# Main.net
KiCad netlist of a schematic drawn in Altium Designer
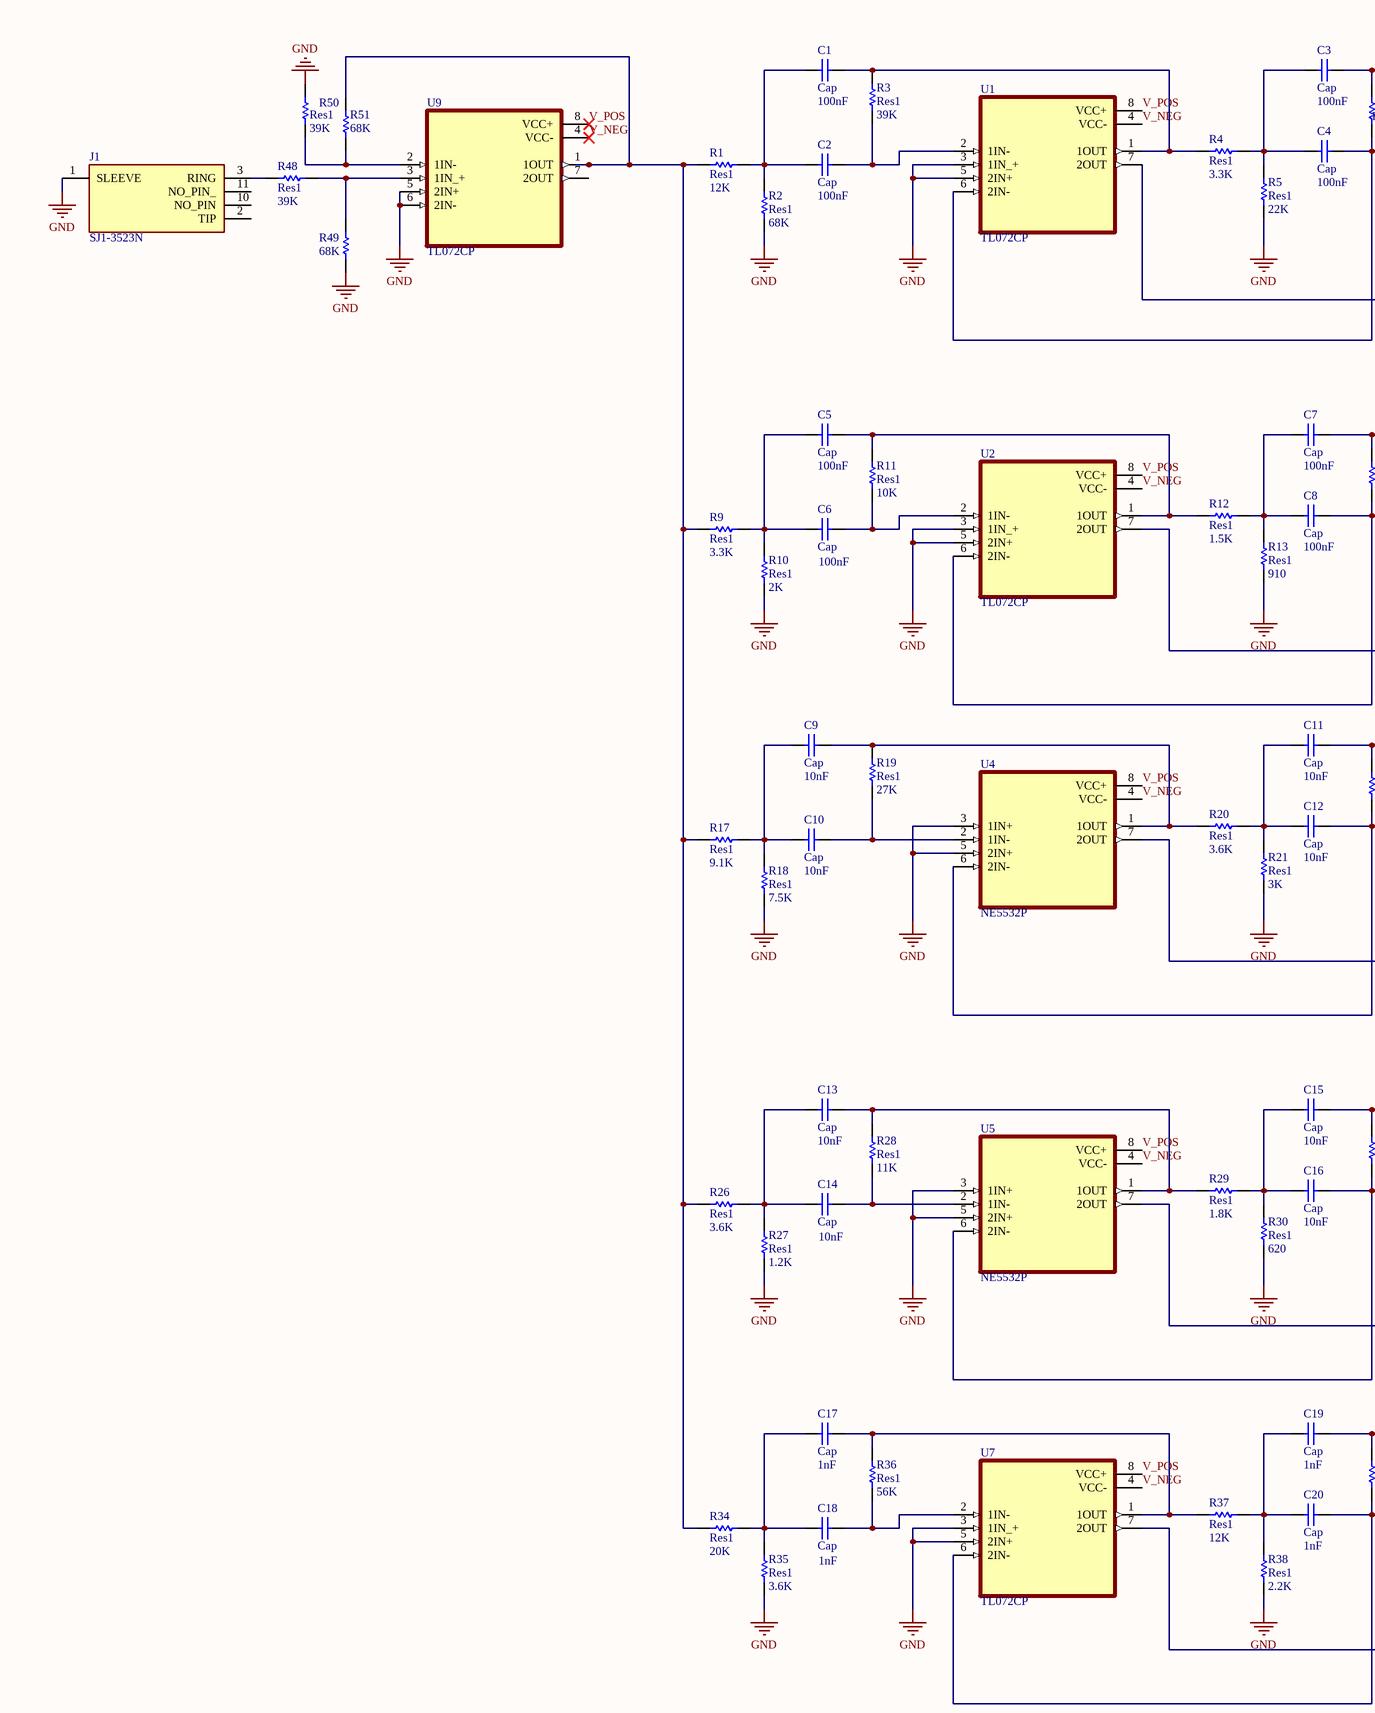
[diagram p0: Main.SchDoc, left]
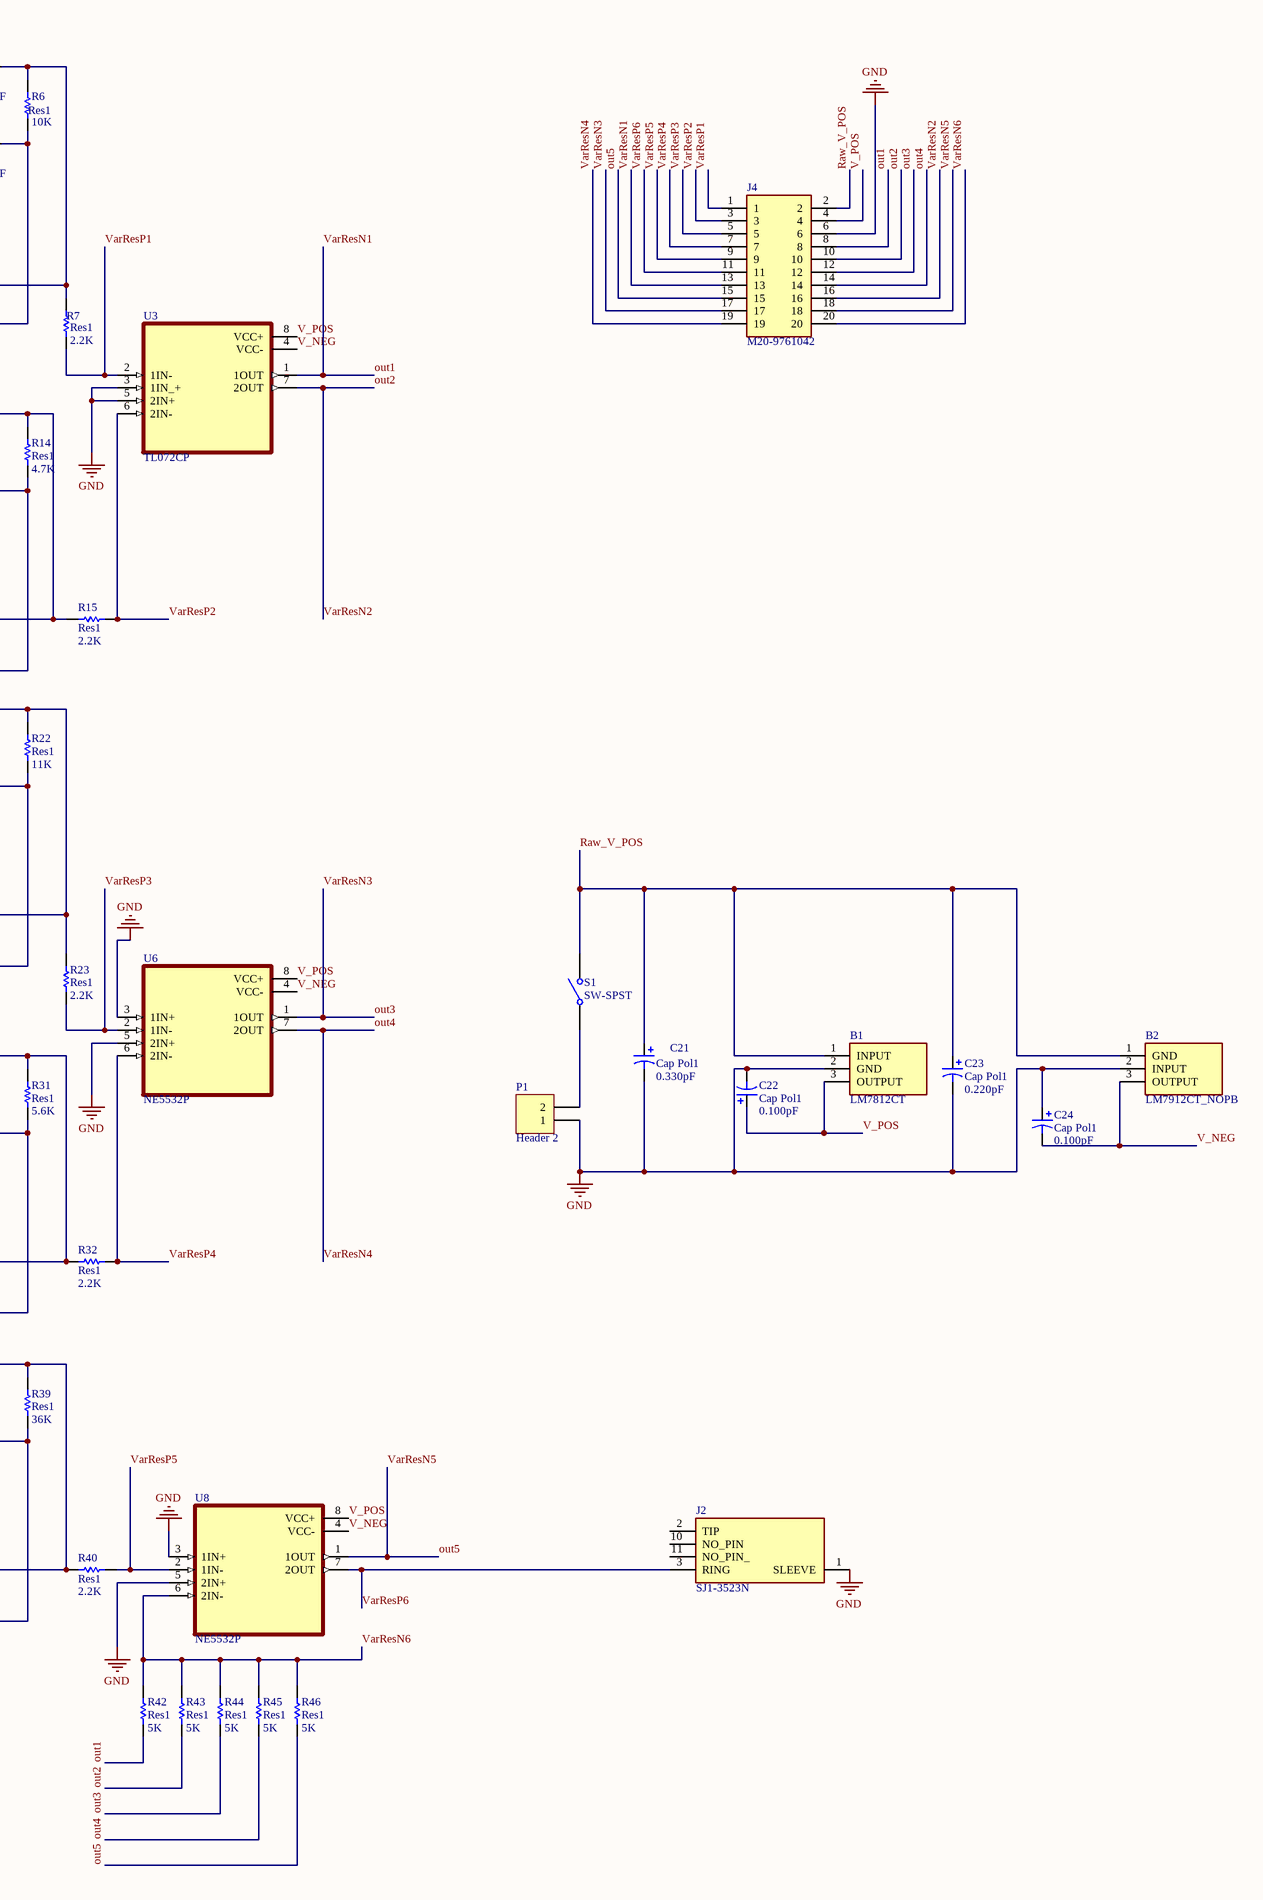
[diagram p1: Main.SchDoc, right]

(export (version "E")
  (design (tool "Eeschema 10.0.6"))
  (components
    (comp (ref "B1")
      (value "LM7812CT")
      (footprint "TO254P470X1028X1955-3P")
      (description "TO220 voltage regulator,LM7812CT 12V 1A")
      (fields (field (name "MOUSER PART NUMBER") "926-LM7812CT"))
      (libsource (lib "LM7812CT") (part "LM7812CT"))
    )
    (comp (ref "B2")
      (value "LM7912CT_NOPB")
      (footprint "TO254P470X1028X1955-3P")
      (description "Texas Instruments LM7912CT/NOPB, Single Negative Voltage Regulator 1.5A -12 V, +/-4%, 3-Pin TO-220")
      (fields
        (field (name "MANUFACTURER_PART_NUMBER") "LM7912CT/NOPB")
        (field (name "MOUSER PART NUMBER") "926-LM7912CT/NOPB")
      )
      (libsource (lib "LM7912CT_NOPB") (part "LM7912CT_NOPB"))
    )
    (comp (ref "C1")
      (value "Cap")
      (footprint "RAD-0.3")
      (description "Capacitor")
      (fields (field (name "ALTIUM_VALUE") "100nF") (field (name "PUBLISHER") "Altium Limited"))
      (libsource (lib "Miscellaneous Devices") (part "Cap"))
    )
    (comp (ref "C2")
      (value "Cap")
      (footprint "RAD-0.3")
      (description "Capacitor")
      (fields (field (name "ALTIUM_VALUE") "100nF") (field (name "PUBLISHER") "Altium Limited"))
      (libsource (lib "Miscellaneous Devices") (part "Cap"))
    )
    (comp (ref "C3")
      (value "Cap")
      (footprint "RAD-0.3")
      (description "Capacitor")
      (fields (field (name "ALTIUM_VALUE") "100nF") (field (name "PUBLISHER") "Altium Limited"))
      (libsource (lib "Miscellaneous Devices") (part "Cap"))
    )
    (comp (ref "C4")
      (value "Cap")
      (footprint "RAD-0.3")
      (description "Capacitor")
      (fields (field (name "ALTIUM_VALUE") "100nF") (field (name "PUBLISHER") "Altium Limited"))
      (libsource (lib "Miscellaneous Devices") (part "Cap"))
    )
    (comp (ref "C5")
      (value "Cap")
      (footprint "RAD-0.3")
      (description "Capacitor")
      (fields (field (name "ALTIUM_VALUE") "100nF") (field (name "PUBLISHER") "Altium Limited"))
      (libsource (lib "Miscellaneous Devices") (part "Cap"))
    )
    (comp (ref "C6")
      (value "Cap")
      (footprint "RAD-0.3")
      (description "Capacitor")
      (fields (field (name "ALTIUM_VALUE") "100nF") (field (name "PUBLISHER") "Altium Limited"))
      (libsource (lib "Miscellaneous Devices") (part "Cap"))
    )
    (comp (ref "C7")
      (value "Cap")
      (footprint "RAD-0.3")
      (description "Capacitor")
      (fields (field (name "ALTIUM_VALUE") "100nF") (field (name "PUBLISHER") "Altium Limited"))
      (libsource (lib "Miscellaneous Devices") (part "Cap"))
    )
    (comp (ref "C8")
      (value "Cap")
      (footprint "RAD-0.3")
      (description "Capacitor")
      (fields (field (name "ALTIUM_VALUE") "100nF") (field (name "PUBLISHER") "Altium Limited"))
      (libsource (lib "Miscellaneous Devices") (part "Cap"))
    )
    (comp (ref "C9")
      (value "Cap")
      (footprint "RAD-0.3")
      (description "Capacitor")
      (fields (field (name "ALTIUM_VALUE") "10nF") (field (name "PUBLISHER") "Altium Limited"))
      (libsource (lib "Miscellaneous Devices") (part "Cap"))
    )
    (comp (ref "C10")
      (value "Cap")
      (footprint "RAD-0.3")
      (description "Capacitor")
      (fields (field (name "ALTIUM_VALUE") "10nF") (field (name "PUBLISHER") "Altium Limited"))
      (libsource (lib "Miscellaneous Devices") (part "Cap"))
    )
    (comp (ref "C11")
      (value "Cap")
      (footprint "RAD-0.3")
      (description "Capacitor")
      (fields (field (name "ALTIUM_VALUE") "10nF") (field (name "PUBLISHER") "Altium Limited"))
      (libsource (lib "Miscellaneous Devices") (part "Cap"))
    )
    (comp (ref "C12")
      (value "Cap")
      (footprint "RAD-0.3")
      (description "Capacitor")
      (fields (field (name "ALTIUM_VALUE") "10nF") (field (name "PUBLISHER") "Altium Limited"))
      (libsource (lib "Miscellaneous Devices") (part "Cap"))
    )
    (comp (ref "C13")
      (value "Cap")
      (footprint "RAD-0.3")
      (description "Capacitor")
      (fields (field (name "ALTIUM_VALUE") "10nF") (field (name "PUBLISHER") "Altium Limited"))
      (libsource (lib "Miscellaneous Devices") (part "Cap"))
    )
    (comp (ref "C14")
      (value "Cap")
      (footprint "RAD-0.3")
      (description "Capacitor")
      (fields (field (name "ALTIUM_VALUE") "10nF") (field (name "PUBLISHER") "Altium Limited"))
      (libsource (lib "Miscellaneous Devices") (part "Cap"))
    )
    (comp (ref "C15")
      (value "Cap")
      (footprint "RAD-0.3")
      (description "Capacitor")
      (fields (field (name "ALTIUM_VALUE") "10nF") (field (name "PUBLISHER") "Altium Limited"))
      (libsource (lib "Miscellaneous Devices") (part "Cap"))
    )
    (comp (ref "C16")
      (value "Cap")
      (footprint "RAD-0.3")
      (description "Capacitor")
      (fields (field (name "ALTIUM_VALUE") "10nF") (field (name "PUBLISHER") "Altium Limited"))
      (libsource (lib "Miscellaneous Devices") (part "Cap"))
    )
    (comp (ref "C17")
      (value "Cap")
      (footprint "RAD-0.3")
      (description "Capacitor")
      (fields (field (name "ALTIUM_VALUE") "1nF") (field (name "PUBLISHER") "Altium Limited"))
      (libsource (lib "Miscellaneous Devices") (part "Cap"))
    )
    (comp (ref "C18")
      (value "Cap")
      (footprint "RAD-0.3")
      (description "Capacitor")
      (fields (field (name "ALTIUM_VALUE") "1nF") (field (name "PUBLISHER") "Altium Limited"))
      (libsource (lib "Miscellaneous Devices") (part "Cap"))
    )
    (comp (ref "C19")
      (value "Cap")
      (footprint "RAD-0.3")
      (description "Capacitor")
      (fields (field (name "ALTIUM_VALUE") "1nF") (field (name "PUBLISHER") "Altium Limited"))
      (libsource (lib "Miscellaneous Devices") (part "Cap"))
    )
    (comp (ref "C20")
      (value "Cap")
      (footprint "RAD-0.3")
      (description "Capacitor")
      (fields (field (name "ALTIUM_VALUE") "1nF") (field (name "PUBLISHER") "Altium Limited"))
      (libsource (lib "Miscellaneous Devices") (part "Cap"))
    )
    (comp (ref "C21")
      (value "Cap Pol1")
      (footprint "RB7.6-15")
      (description "Polarized Capacitor (Radial)")
      (fields (field (name "ALTIUM_VALUE") "0.330pF") (field (name "PUBLISHER") "Altium Limited"))
      (libsource (lib "Miscellaneous Devices") (part "Cap Pol1"))
    )
    (comp (ref "C22")
      (value "Cap Pol1")
      (footprint "RB7.6-15")
      (description "Polarized Capacitor (Radial)")
      (fields (field (name "ALTIUM_VALUE") "0.100pF") (field (name "PUBLISHER") "Altium Limited"))
      (libsource (lib "Miscellaneous Devices") (part "Cap Pol1"))
    )
    (comp (ref "C23")
      (value "Cap Pol1")
      (footprint "RB7.6-15")
      (description "Polarized Capacitor (Radial)")
      (fields (field (name "ALTIUM_VALUE") "0.220pF") (field (name "PUBLISHER") "Altium Limited"))
      (libsource (lib "Miscellaneous Devices") (part "Cap Pol1"))
    )
    (comp (ref "C24")
      (value "Cap Pol1")
      (footprint "RB7.6-15")
      (description "Polarized Capacitor (Radial)")
      (fields (field (name "ALTIUM_VALUE") "0.100pF") (field (name "PUBLISHER") "Altium Limited"))
      (libsource (lib "Miscellaneous Devices") (part "Cap Pol1"))
    )
    (comp (ref "J1")
      (value "SJ1-3523N")
      (footprint "SJ13523N")
      (description "Phone Connectors 3.5 MM AUDIO JACK")
      (fields (field (name "MOUSER PART NUMBER") "490-SJ1-3523N"))
      (libsource (lib "") (part "SJ1-3523N_1"))
    )
    (comp (ref "J2")
      (value "SJ1-3523N")
      (footprint "SJ13523N")
      (description "Phone Connectors 3.5 MM AUDIO JACK")
      (fields (field (name "MOUSER PART NUMBER") "490-SJ1-3523N"))
      (libsource (lib "SJ1-3523N") (part "SJ1-3523N"))
    )
    (comp (ref "J4")
      (value "M20-9761042")
      (footprint "HDRV20W64P254_2X10_2540X508X838P")
      (description "Headers & Wire Housings 10+10 DIL VERTICAL PIN HEADER GOLD+TIN")
      (fields (field (name "MOUSER PART NUMBER") "855-M20-9761042"))
      (libsource (lib "M20-9761042") (part "M20-9761042"))
    )
    (comp (ref "P1")
      (value "Header 2")
      (footprint "HDR1X2")
      (description "Header, 2-Pin")
      (fields (field (name "PUBLISHER") "Altium Limited"))
      (libsource (lib "Miscellaneous Connectors") (part "Header 2"))
    )
    (comp (ref "R1")
      (value "Res1")
      (footprint "AXIAL-0.3")
      (description "Resistor")
      (fields (field (name "ALTIUM_VALUE") "12K") (field (name "PUBLISHER") "Altium Limited"))
      (libsource (lib "Miscellaneous Devices") (part "Res1"))
    )
    (comp (ref "R2")
      (value "Res1")
      (footprint "AXIAL-0.3")
      (description "Resistor")
      (fields (field (name "ALTIUM_VALUE") "68K") (field (name "PUBLISHER") "Altium Limited"))
      (libsource (lib "Miscellaneous Devices") (part "Res1"))
    )
    (comp (ref "R3")
      (value "Res1")
      (footprint "AXIAL-0.3")
      (description "Resistor")
      (fields (field (name "ALTIUM_VALUE") "39K") (field (name "PUBLISHER") "Altium Limited"))
      (libsource (lib "Miscellaneous Devices") (part "Res1"))
    )
    (comp (ref "R4")
      (value "Res1")
      (footprint "AXIAL-0.3")
      (description "Resistor")
      (fields (field (name "ALTIUM_VALUE") "3.3K") (field (name "PUBLISHER") "Altium Limited"))
      (libsource (lib "Miscellaneous Devices") (part "Res1"))
    )
    (comp (ref "R5")
      (value "Res1")
      (footprint "AXIAL-0.3")
      (description "Resistor")
      (fields (field (name "ALTIUM_VALUE") "22K") (field (name "PUBLISHER") "Altium Limited"))
      (libsource (lib "Miscellaneous Devices") (part "Res1"))
    )
    (comp (ref "R6")
      (value "Res1")
      (footprint "AXIAL-0.3")
      (description "Resistor")
      (fields (field (name "ALTIUM_VALUE") "10K") (field (name "PUBLISHER") "Altium Limited"))
      (libsource (lib "Miscellaneous Devices") (part "Res1"))
    )
    (comp (ref "R7")
      (value "Res1")
      (footprint "AXIAL-0.3")
      (description "Resistor")
      (fields (field (name "ALTIUM_VALUE") "2.2K") (field (name "PUBLISHER") "Altium Limited"))
      (libsource (lib "Miscellaneous Devices") (part "Res1"))
    )
    (comp (ref "R9")
      (value "Res1")
      (footprint "AXIAL-0.3")
      (description "Resistor")
      (fields (field (name "ALTIUM_VALUE") "3.3K") (field (name "PUBLISHER") "Altium Limited"))
      (libsource (lib "") (part "Res1_1"))
    )
    (comp (ref "R10")
      (value "Res1")
      (footprint "AXIAL-0.3")
      (description "Resistor")
      (fields (field (name "ALTIUM_VALUE") "2K") (field (name "PUBLISHER") "Altium Limited"))
      (libsource (lib "Miscellaneous Devices") (part "Res1"))
    )
    (comp (ref "R11")
      (value "Res1")
      (footprint "AXIAL-0.3")
      (description "Resistor")
      (fields (field (name "ALTIUM_VALUE") "10K") (field (name "PUBLISHER") "Altium Limited"))
      (libsource (lib "Miscellaneous Devices") (part "Res1"))
    )
    (comp (ref "R12")
      (value "Res1")
      (footprint "AXIAL-0.3")
      (description "Resistor")
      (fields (field (name "ALTIUM_VALUE") "1.5K") (field (name "PUBLISHER") "Altium Limited"))
      (libsource (lib "") (part "Res1_1"))
    )
    (comp (ref "R13")
      (value "Res1")
      (footprint "AXIAL-0.3")
      (description "Resistor")
      (fields (field (name "ALTIUM_VALUE") "910") (field (name "PUBLISHER") "Altium Limited"))
      (libsource (lib "Miscellaneous Devices") (part "Res1"))
    )
    (comp (ref "R14")
      (value "Res1")
      (footprint "AXIAL-0.3")
      (description "Resistor")
      (fields (field (name "ALTIUM_VALUE") "4.7K") (field (name "PUBLISHER") "Altium Limited"))
      (libsource (lib "Miscellaneous Devices") (part "Res1"))
    )
    (comp (ref "R15")
      (value "Res1")
      (footprint "AXIAL-0.3")
      (description "Resistor")
      (fields (field (name "ALTIUM_VALUE") "2.2K") (field (name "PUBLISHER") "Altium Limited"))
      (libsource (lib "") (part "Res1_1"))
    )
    (comp (ref "R17")
      (value "Res1")
      (footprint "AXIAL-0.3")
      (description "Resistor")
      (fields (field (name "ALTIUM_VALUE") "9.1K") (field (name "PUBLISHER") "Altium Limited"))
      (libsource (lib "Miscellaneous Devices") (part "Res1"))
    )
    (comp (ref "R18")
      (value "Res1")
      (footprint "AXIAL-0.3")
      (description "Resistor")
      (fields (field (name "ALTIUM_VALUE") "7.5K") (field (name "PUBLISHER") "Altium Limited"))
      (libsource (lib "Miscellaneous Devices") (part "Res1"))
    )
    (comp (ref "R19")
      (value "Res1")
      (footprint "AXIAL-0.3")
      (description "Resistor")
      (fields (field (name "ALTIUM_VALUE") "27K") (field (name "PUBLISHER") "Altium Limited"))
      (libsource (lib "Miscellaneous Devices") (part "Res1"))
    )
    (comp (ref "R20")
      (value "Res1")
      (footprint "AXIAL-0.3")
      (description "Resistor")
      (fields (field (name "ALTIUM_VALUE") "3.6K") (field (name "PUBLISHER") "Altium Limited"))
      (libsource (lib "Miscellaneous Devices") (part "Res1"))
    )
    (comp (ref "R21")
      (value "Res1")
      (footprint "AXIAL-0.3")
      (description "Resistor")
      (fields (field (name "ALTIUM_VALUE") "3K") (field (name "PUBLISHER") "Altium Limited"))
      (libsource (lib "Miscellaneous Devices") (part "Res1"))
    )
    (comp (ref "R22")
      (value "Res1")
      (footprint "AXIAL-0.3")
      (description "Resistor")
      (fields (field (name "ALTIUM_VALUE") "11K") (field (name "PUBLISHER") "Altium Limited"))
      (libsource (lib "Miscellaneous Devices") (part "Res1"))
    )
    (comp (ref "R23")
      (value "Res1")
      (footprint "AXIAL-0.3")
      (description "Resistor")
      (fields (field (name "ALTIUM_VALUE") "2.2K") (field (name "PUBLISHER") "Altium Limited"))
      (libsource (lib "Miscellaneous Devices") (part "Res1"))
    )
    (comp (ref "R26")
      (value "Res1")
      (footprint "AXIAL-0.3")
      (description "Resistor")
      (fields (field (name "ALTIUM_VALUE") "3.6K") (field (name "PUBLISHER") "Altium Limited"))
      (libsource (lib "Miscellaneous Devices") (part "Res1"))
    )
    (comp (ref "R27")
      (value "Res1")
      (footprint "AXIAL-0.3")
      (description "Resistor")
      (fields (field (name "ALTIUM_VALUE") "1.2K") (field (name "PUBLISHER") "Altium Limited"))
      (libsource (lib "Miscellaneous Devices") (part "Res1"))
    )
    (comp (ref "R28")
      (value "Res1")
      (footprint "AXIAL-0.3")
      (description "Resistor")
      (fields (field (name "ALTIUM_VALUE") "11K") (field (name "PUBLISHER") "Altium Limited"))
      (libsource (lib "Miscellaneous Devices") (part "Res1"))
    )
    (comp (ref "R29")
      (value "Res1")
      (footprint "AXIAL-0.3")
      (description "Resistor")
      (fields (field (name "ALTIUM_VALUE") "1.8K") (field (name "PUBLISHER") "Altium Limited"))
      (libsource (lib "Miscellaneous Devices") (part "Res1"))
    )
    (comp (ref "R30")
      (value "Res1")
      (footprint "AXIAL-0.3")
      (description "Resistor")
      (fields (field (name "ALTIUM_VALUE") "620") (field (name "PUBLISHER") "Altium Limited"))
      (libsource (lib "Miscellaneous Devices") (part "Res1"))
    )
    (comp (ref "R31")
      (value "Res1")
      (footprint "AXIAL-0.3")
      (description "Resistor")
      (fields (field (name "ALTIUM_VALUE") "5.6K") (field (name "PUBLISHER") "Altium Limited"))
      (libsource (lib "Miscellaneous Devices") (part "Res1"))
    )
    (comp (ref "R32")
      (value "Res1")
      (footprint "AXIAL-0.3")
      (description "Resistor")
      (fields (field (name "ALTIUM_VALUE") "2.2K") (field (name "PUBLISHER") "Altium Limited"))
      (libsource (lib "Miscellaneous Devices") (part "Res1"))
    )
    (comp (ref "R34")
      (value "Res1")
      (footprint "AXIAL-0.3")
      (description "Resistor")
      (fields (field (name "ALTIUM_VALUE") "20K") (field (name "PUBLISHER") "Altium Limited"))
      (libsource (lib "Miscellaneous Devices") (part "Res1"))
    )
    (comp (ref "R35")
      (value "Res1")
      (footprint "AXIAL-0.3")
      (description "Resistor")
      (fields (field (name "ALTIUM_VALUE") "3.6K") (field (name "PUBLISHER") "Altium Limited"))
      (libsource (lib "Miscellaneous Devices") (part "Res1"))
    )
    (comp (ref "R36")
      (value "Res1")
      (footprint "AXIAL-0.3")
      (description "Resistor")
      (fields (field (name "ALTIUM_VALUE") "56K") (field (name "PUBLISHER") "Altium Limited"))
      (libsource (lib "Miscellaneous Devices") (part "Res1"))
    )
    (comp (ref "R37")
      (value "Res1")
      (footprint "AXIAL-0.3")
      (description "Resistor")
      (fields (field (name "ALTIUM_VALUE") "12K") (field (name "PUBLISHER") "Altium Limited"))
      (libsource (lib "Miscellaneous Devices") (part "Res1"))
    )
    (comp (ref "R38")
      (value "Res1")
      (footprint "AXIAL-0.3")
      (description "Resistor")
      (fields (field (name "ALTIUM_VALUE") "2.2K") (field (name "PUBLISHER") "Altium Limited"))
      (libsource (lib "Miscellaneous Devices") (part "Res1"))
    )
    (comp (ref "R39")
      (value "Res1")
      (footprint "AXIAL-0.3")
      (description "Resistor")
      (fields (field (name "ALTIUM_VALUE") "36K") (field (name "PUBLISHER") "Altium Limited"))
      (libsource (lib "") (part "Res1_1"))
    )
    (comp (ref "R40")
      (value "Res1")
      (footprint "AXIAL-0.3")
      (description "Resistor")
      (fields (field (name "ALTIUM_VALUE") "2.2K") (field (name "PUBLISHER") "Altium Limited"))
      (libsource (lib "Miscellaneous Devices") (part "Res1"))
    )
    (comp (ref "R42")
      (value "Res1")
      (footprint "AXIAL-0.3")
      (description "Resistor")
      (fields (field (name "ALTIUM_VALUE") "5K") (field (name "PUBLISHER") "Altium Limited"))
      (libsource (lib "Miscellaneous Devices") (part "Res1"))
    )
    (comp (ref "R43")
      (value "Res1")
      (footprint "AXIAL-0.3")
      (description "Resistor")
      (fields (field (name "ALTIUM_VALUE") "5K") (field (name "PUBLISHER") "Altium Limited"))
      (libsource (lib "Miscellaneous Devices") (part "Res1"))
    )
    (comp (ref "R44")
      (value "Res1")
      (footprint "AXIAL-0.3")
      (description "Resistor")
      (fields (field (name "ALTIUM_VALUE") "5K") (field (name "PUBLISHER") "Altium Limited"))
      (libsource (lib "Miscellaneous Devices") (part "Res1"))
    )
    (comp (ref "R45")
      (value "Res1")
      (footprint "AXIAL-0.3")
      (description "Resistor")
      (fields (field (name "ALTIUM_VALUE") "5K") (field (name "PUBLISHER") "Altium Limited"))
      (libsource (lib "Miscellaneous Devices") (part "Res1"))
    )
    (comp (ref "R46")
      (value "Res1")
      (footprint "AXIAL-0.3")
      (description "Resistor")
      (fields (field (name "ALTIUM_VALUE") "5K") (field (name "PUBLISHER") "Altium Limited"))
      (libsource (lib "Miscellaneous Devices") (part "Res1"))
    )
    (comp (ref "R48")
      (value "Res1")
      (footprint "AXIAL-0.3")
      (description "Resistor")
      (fields (field (name "ALTIUM_VALUE") "39K") (field (name "PUBLISHER") "Altium Limited"))
      (libsource (lib "Miscellaneous Devices") (part "Res1"))
    )
    (comp (ref "R49")
      (value "68K")
      (footprint "AXIAL-0.3")
      (description "Resistor")
      (fields (field (name "Comment") "Res1") (field (name "PUBLISHER") "Altium Limited"))
      (libsource (lib "Miscellaneous Devices") (part "Res1"))
    )
    (comp (ref "R50")
      (value "Res1")
      (footprint "AXIAL-0.3")
      (description "Resistor")
      (fields (field (name "ALTIUM_VALUE") "39K") (field (name "PUBLISHER") "Altium Limited"))
      (libsource (lib "Miscellaneous Devices") (part "Res1"))
    )
    (comp (ref "R51")
      (value "68K")
      (footprint "AXIAL-0.3")
      (description "Resistor")
      (fields (field (name "Comment") "Res1") (field (name "PUBLISHER") "Altium Limited"))
      (libsource (lib "Miscellaneous Devices") (part "Res1"))
    )
    (comp (ref "S1")
      (value "SW-SPST")
      (footprint "SPST-2")
      (description "Single-Pole, Single-Throw Switch")
      (fields (field (name "PUBLISHER") "Altium Limited"))
      (libsource (lib "Miscellaneous Devices") (part "SW-SPST"))
    )
    (comp (ref "U1")
      (value "TL072CP")
      (footprint "DIP794W45P254L959H508Q8")
      (description "Dual Low-Noise JFET-Input General-Purpose Operational Amplifier")
      (fields (field (name "MF") "Texas Instruments"))
      (libsource (lib "TL072CP") (part "TL072CP"))
    )
    (comp (ref "U2")
      (value "TL072CP")
      (footprint "DIP794W45P254L959H508Q8")
      (description "Dual Low-Noise JFET-Input General-Purpose Operational Amplifier")
      (fields (field (name "MF") "Texas Instruments"))
      (libsource (lib "TL072CP") (part "TL072CP"))
    )
    (comp (ref "U3")
      (value "TL072CP")
      (footprint "DIP794W45P254L959H508Q8")
      (description "Dual Low-Noise JFET-Input General-Purpose Operational Amplifier")
      (fields (field (name "MF") "Texas Instruments"))
      (libsource (lib "TL072CP") (part "TL072CP"))
    )
    (comp (ref "U4")
      (value "NE5532P")
      (footprint "DIP794W45P254L959H508Q8")
      (description "Dual Low-Noise High-Speed Audio Operational Amplifier 8-PDIP 0 to 70")
      (fields (field (name "MF") "Texas Instruments"))
      (libsource (lib "NE5532P") (part "NE5532P"))
    )
    (comp (ref "U5")
      (value "NE5532P")
      (footprint "DIP794W45P254L959H508Q8")
      (description "Dual Low-Noise High-Speed Audio Operational Amplifier 8-PDIP 0 to 70")
      (fields (field (name "MF") "Texas Instruments"))
      (libsource (lib "NE5532P") (part "NE5532P"))
    )
    (comp (ref "U6")
      (value "NE5532P")
      (footprint "DIP794W45P254L959H508Q8")
      (description "Dual Low-Noise High-Speed Audio Operational Amplifier 8-PDIP 0 to 70")
      (fields (field (name "MF") "Texas Instruments"))
      (libsource (lib "NE5532P") (part "NE5532P"))
    )
    (comp (ref "U7")
      (value "TL072CP")
      (footprint "DIP794W45P254L959H508Q8")
      (description "Dual Low-Noise JFET-Input General-Purpose Operational Amplifier")
      (fields (field (name "MF") "Texas Instruments"))
      (libsource (lib "TL072CP") (part "TL072CP"))
    )
    (comp (ref "U8")
      (value "NE5532P")
      (footprint "DIP794W45P254L959H508Q8")
      (description "Dual Low-Noise High-Speed Audio Operational Amplifier 8-PDIP 0 to 70")
      (fields (field (name "MF") "Texas Instruments"))
      (libsource (lib "NE5532P") (part "NE5532P"))
    )
    (comp (ref "U9")
      (value "TL072CP")
      (footprint "DIP794W45P254L959H508Q8")
      (description "Dual Low-Noise JFET-Input General-Purpose Operational Amplifier")
      (fields (field (name "MF") "Texas Instruments"))
      (libsource (lib "TL072CP") (part "TL072CP"))
    )
  )
  (nets
    (net (code "1") (name "/Raw_V_POS") (class "Default")
      (node (ref "B1") (pin "1") (pinfunction "INPUT_1") (pintype "passive"))
      (node (ref "B2") (pin "1") (pinfunction "GND_1") (pintype "passive"))
      (node (ref "C21") (pin "1") (pinfunction "1_1") (pintype "passive"))
      (node (ref "C23") (pin "1") (pinfunction "1_1") (pintype "passive"))
      (node (ref "J4") (pin "2") (pinfunction "2_2") (pintype "passive"))
      (node (ref "S1") (pin "2") (pinfunction "NO_2") (pintype "passive"))
    )
    (net (code "2") (name "/V_NEG") (class "Default")
      (node (ref "B2") (pin "3") (pinfunction "OUTPUT_3") (pintype "passive"))
      (node (ref "C24") (pin "2") (pinfunction "2_2") (pintype "passive"))
      (node (ref "U1") (pin "4") (pinfunction "VCC-_4") (pintype "power_in"))
      (node (ref "U2") (pin "4") (pinfunction "VCC-_4") (pintype "power_in"))
      (node (ref "U3") (pin "4") (pinfunction "VCC-_4") (pintype "power_in"))
      (node (ref "U4") (pin "4") (pinfunction "VCC-_4") (pintype "power_in"))
      (node (ref "U5") (pin "4") (pinfunction "VCC-_4") (pintype "power_in"))
      (node (ref "U6") (pin "4") (pinfunction "VCC-_4") (pintype "power_in"))
      (node (ref "U7") (pin "4") (pinfunction "VCC-_4") (pintype "power_in"))
      (node (ref "U8") (pin "4") (pinfunction "VCC-_4") (pintype "power_in"))
      (node (ref "U9") (pin "4") (pinfunction "VCC-_4") (pintype "power_in"))
    )
    (net (code "3") (name "/V_POS") (class "Default")
      (node (ref "B1") (pin "3") (pinfunction "OUTPUT_3") (pintype "passive"))
      (node (ref "C22") (pin "1") (pinfunction "1_1") (pintype "passive"))
      (node (ref "J4") (pin "4") (pinfunction "4_4") (pintype "passive"))
      (node (ref "U1") (pin "8") (pinfunction "VCC+_8") (pintype "power_in"))
      (node (ref "U2") (pin "8") (pinfunction "VCC+_8") (pintype "power_in"))
      (node (ref "U3") (pin "8") (pinfunction "VCC+_8") (pintype "power_in"))
      (node (ref "U4") (pin "8") (pinfunction "VCC+_8") (pintype "power_in"))
      (node (ref "U5") (pin "8") (pinfunction "VCC+_8") (pintype "power_in"))
      (node (ref "U6") (pin "8") (pinfunction "VCC+_8") (pintype "power_in"))
      (node (ref "U7") (pin "8") (pinfunction "VCC+_8") (pintype "power_in"))
      (node (ref "U8") (pin "8") (pinfunction "VCC+_8") (pintype "power_in"))
      (node (ref "U9") (pin "8") (pinfunction "VCC+_8") (pintype "power_in"))
    )
    (net (code "4") (name "/VarResN1") (class "Default")
      (node (ref "J4") (pin "13") (pinfunction "13_13") (pintype "passive"))
      (node (ref "J4") (pin "8") (pinfunction "8_8") (pintype "passive"))
      (node (ref "R42") (pin "1") (pinfunction "1_1") (pintype "passive"))
      (node (ref "U3") (pin "1") (pinfunction "1OUT_1") (pintype "output"))
    )
    (net (code "5") (name "/VarResN2") (class "Default")
      (node (ref "J4") (pin "10") (pinfunction "10_10") (pintype "passive"))
      (node (ref "J4") (pin "16") (pinfunction "16_16") (pintype "passive"))
      (node (ref "R43") (pin "1") (pinfunction "1_1") (pintype "passive"))
      (node (ref "U3") (pin "7") (pinfunction "2OUT_7") (pintype "output"))
    )
    (net (code "6") (name "/VarResN3") (class "Default")
      (node (ref "J4") (pin "12") (pinfunction "12_12") (pintype "passive"))
      (node (ref "J4") (pin "17") (pinfunction "17_17") (pintype "passive"))
      (node (ref "R44") (pin "1") (pinfunction "1_1") (pintype "passive"))
      (node (ref "U6") (pin "1") (pinfunction "1OUT_1") (pintype "output"))
    )
    (net (code "7") (name "/VarResN4") (class "Default")
      (node (ref "J4") (pin "14") (pinfunction "14_14") (pintype "passive"))
      (node (ref "J4") (pin "19") (pinfunction "19_19") (pintype "passive"))
      (node (ref "R45") (pin "1") (pinfunction "1_1") (pintype "passive"))
      (node (ref "U6") (pin "7") (pinfunction "2OUT_7") (pintype "output"))
    )
    (net (code "8") (name "/VarResN5") (class "Default")
      (node (ref "J4") (pin "15") (pinfunction "15_15") (pintype "passive"))
      (node (ref "J4") (pin "18") (pinfunction "18_18") (pintype "passive"))
      (node (ref "R46") (pin "1") (pinfunction "1_1") (pintype "passive"))
      (node (ref "U8") (pin "1") (pinfunction "1OUT_1") (pintype "output"))
    )
    (net (code "9") (name "/VarResN6") (class "Default")
      (node (ref "J4") (pin "20") (pinfunction "20_20") (pintype "passive"))
      (node (ref "R42") (pin "2") (pinfunction "2_2") (pintype "passive"))
      (node (ref "R43") (pin "2") (pinfunction "2_2") (pintype "passive"))
      (node (ref "R44") (pin "2") (pinfunction "2_2") (pintype "passive"))
      (node (ref "R45") (pin "2") (pinfunction "2_2") (pintype "passive"))
      (node (ref "R46") (pin "2") (pinfunction "2_2") (pintype "passive"))
      (node (ref "U8") (pin "6") (pinfunction "2IN-_6") (pintype "input"))
    )
    (net (code "10") (name "/VarResP1") (class "Default")
      (node (ref "J4") (pin "1") (pinfunction "1_1") (pintype "passive"))
      (node (ref "R7") (pin "1") (pinfunction "1_1") (pintype "passive"))
      (node (ref "U3") (pin "2") (pinfunction "1IN-_2") (pintype "input"))
    )
    (net (code "11") (name "/VarResP2") (class "Default")
      (node (ref "J4") (pin "3") (pinfunction "3_3") (pintype "passive"))
      (node (ref "R15") (pin "2") (pinfunction "2_2") (pintype "passive"))
      (node (ref "U3") (pin "6") (pinfunction "2IN-_6") (pintype "input"))
    )
    (net (code "12") (name "/VarResP3") (class "Default")
      (node (ref "J4") (pin "5") (pinfunction "5_5") (pintype "passive"))
      (node (ref "R23") (pin "1") (pinfunction "1_1") (pintype "passive"))
      (node (ref "U6") (pin "2") (pinfunction "1IN-_2") (pintype "input"))
    )
    (net (code "13") (name "/VarResP4") (class "Default")
      (node (ref "J4") (pin "7") (pinfunction "7_7") (pintype "passive"))
      (node (ref "R32") (pin "1") (pinfunction "1_1") (pintype "passive"))
      (node (ref "U6") (pin "6") (pinfunction "2IN-_6") (pintype "input"))
    )
    (net (code "14") (name "/VarResP5") (class "Default")
      (node (ref "J4") (pin "9") (pinfunction "9_9") (pintype "passive"))
      (node (ref "R40") (pin "1") (pinfunction "1_1") (pintype "passive"))
      (node (ref "U8") (pin "2") (pinfunction "1IN-_2") (pintype "input"))
    )
    (net (code "15") (name "/VarResP6") (class "Default")
      (node (ref "J2") (pin "3") (pinfunction "RING_3") (pintype "passive"))
      (node (ref "J4") (pin "11") (pinfunction "11_11") (pintype "passive"))
      (node (ref "U8") (pin "7") (pinfunction "2OUT_7") (pintype "output"))
    )
    (net (code "16") (name "GND") (class "Default")
      (node (ref "B1") (pin "2") (pinfunction "GND_2") (pintype "passive"))
      (node (ref "B2") (pin "2") (pinfunction "INPUT_2") (pintype "passive"))
      (node (ref "C21") (pin "2") (pinfunction "2_2") (pintype "passive"))
      (node (ref "C22") (pin "2") (pinfunction "2_2") (pintype "passive"))
      (node (ref "C23") (pin "2") (pinfunction "2_2") (pintype "passive"))
      (node (ref "C24") (pin "1") (pinfunction "1_1") (pintype "passive"))
      (node (ref "J1") (pin "1") (pinfunction "SLEEVE_1") (pintype "passive"))
      (node (ref "J2") (pin "1") (pinfunction "SLEEVE_1") (pintype "passive"))
      (node (ref "J4") (pin "6") (pinfunction "6_6") (pintype "passive"))
      (node (ref "P1") (pin "1") (pinfunction "1_1") (pintype "passive"))
      (node (ref "R10") (pin "1") (pinfunction "1_1") (pintype "passive"))
      (node (ref "R13") (pin "1") (pinfunction "1_1") (pintype "passive"))
      (node (ref "R18") (pin "1") (pinfunction "1_1") (pintype "passive"))
      (node (ref "R2") (pin "1") (pinfunction "1_1") (pintype "passive"))
      (node (ref "R21") (pin "1") (pinfunction "1_1") (pintype "passive"))
      (node (ref "R27") (pin "1") (pinfunction "1_1") (pintype "passive"))
      (node (ref "R30") (pin "1") (pinfunction "1_1") (pintype "passive"))
      (node (ref "R35") (pin "1") (pinfunction "1_1") (pintype "passive"))
      (node (ref "R38") (pin "1") (pinfunction "1_1") (pintype "passive"))
      (node (ref "R49") (pin "2") (pinfunction "2_2") (pintype "passive"))
      (node (ref "R5") (pin "1") (pinfunction "1_1") (pintype "passive"))
      (node (ref "R50") (pin "2") (pinfunction "2_2") (pintype "passive"))
      (node (ref "U1") (pin "3") (pinfunction "1IN_+_3") (pintype "input"))
      (node (ref "U1") (pin "5") (pinfunction "2IN+_5") (pintype "input"))
      (node (ref "U2") (pin "3") (pinfunction "1IN_+_3") (pintype "input"))
      (node (ref "U2") (pin "5") (pinfunction "2IN+_5") (pintype "input"))
      (node (ref "U3") (pin "3") (pinfunction "1IN_+_3") (pintype "input"))
      (node (ref "U3") (pin "5") (pinfunction "2IN+_5") (pintype "input"))
      (node (ref "U4") (pin "3") (pinfunction "1IN+_3") (pintype "input"))
      (node (ref "U4") (pin "5") (pinfunction "2IN+_5") (pintype "input"))
      (node (ref "U5") (pin "3") (pinfunction "1IN+_3") (pintype "input"))
      (node (ref "U5") (pin "5") (pinfunction "2IN+_5") (pintype "input"))
      (node (ref "U6") (pin "3") (pinfunction "1IN+_3") (pintype "input"))
      (node (ref "U6") (pin "5") (pinfunction "2IN+_5") (pintype "input"))
      (node (ref "U7") (pin "3") (pinfunction "1IN_+_3") (pintype "input"))
      (node (ref "U7") (pin "5") (pinfunction "2IN+_5") (pintype "input"))
      (node (ref "U8") (pin "3") (pinfunction "1IN+_3") (pintype "input"))
      (node (ref "U8") (pin "5") (pinfunction "2IN+_5") (pintype "input"))
      (node (ref "U9") (pin "5") (pinfunction "2IN+_5") (pintype "input"))
      (node (ref "U9") (pin "6") (pinfunction "2IN-_6") (pintype "input"))
    )
    (net (code "17") (name "Net-(C1-Pad1)") (class "Default")
      (node (ref "C1") (pin "1") (pinfunction "1_1") (pintype "passive"))
      (node (ref "C2") (pin "1") (pinfunction "1_1") (pintype "passive"))
      (node (ref "R1") (pin "2") (pinfunction "2_2") (pintype "passive"))
      (node (ref "R2") (pin "2") (pinfunction "2_2") (pintype "passive"))
    )
    (net (code "18") (name "Net-(C3-Pad1)") (class "Default")
      (node (ref "C3") (pin "1") (pinfunction "1_1") (pintype "passive"))
      (node (ref "C4") (pin "1") (pinfunction "1_1") (pintype "passive"))
      (node (ref "R4") (pin "2") (pinfunction "2_2") (pintype "passive"))
      (node (ref "R5") (pin "2") (pinfunction "2_2") (pintype "passive"))
    )
    (net (code "19") (name "Net-(C5-Pad1)") (class "Default")
      (node (ref "C5") (pin "1") (pinfunction "1_1") (pintype "passive"))
      (node (ref "C6") (pin "1") (pinfunction "1_1") (pintype "passive"))
      (node (ref "R10") (pin "2") (pinfunction "2_2") (pintype "passive"))
      (node (ref "R9") (pin "1") (pinfunction "1_1") (pintype "passive"))
    )
    (net (code "20") (name "Net-(C7-Pad1)") (class "Default")
      (node (ref "C7") (pin "1") (pinfunction "1_1") (pintype "passive"))
      (node (ref "C8") (pin "1") (pinfunction "1_1") (pintype "passive"))
      (node (ref "R12") (pin "1") (pinfunction "1_1") (pintype "passive"))
      (node (ref "R13") (pin "2") (pinfunction "2_2") (pintype "passive"))
    )
    (net (code "21") (name "Net-(C10-Pad1)") (class "Default")
      (node (ref "C10") (pin "1") (pinfunction "1_1") (pintype "passive"))
      (node (ref "C9") (pin "1") (pinfunction "1_1") (pintype "passive"))
      (node (ref "R17") (pin "2") (pinfunction "2_2") (pintype "passive"))
      (node (ref "R18") (pin "2") (pinfunction "2_2") (pintype "passive"))
    )
    (net (code "22") (name "Net-(C11-Pad1)") (class "Default")
      (node (ref "C11") (pin "1") (pinfunction "1_1") (pintype "passive"))
      (node (ref "C12") (pin "1") (pinfunction "1_1") (pintype "passive"))
      (node (ref "R20") (pin "2") (pinfunction "2_2") (pintype "passive"))
      (node (ref "R21") (pin "2") (pinfunction "2_2") (pintype "passive"))
    )
    (net (code "23") (name "Net-(C13-Pad1)") (class "Default")
      (node (ref "C13") (pin "1") (pinfunction "1_1") (pintype "passive"))
      (node (ref "C14") (pin "1") (pinfunction "1_1") (pintype "passive"))
      (node (ref "R26") (pin "2") (pinfunction "2_2") (pintype "passive"))
      (node (ref "R27") (pin "2") (pinfunction "2_2") (pintype "passive"))
    )
    (net (code "24") (name "Net-(C15-Pad1)") (class "Default")
      (node (ref "C15") (pin "1") (pinfunction "1_1") (pintype "passive"))
      (node (ref "C16") (pin "1") (pinfunction "1_1") (pintype "passive"))
      (node (ref "R29") (pin "2") (pinfunction "2_2") (pintype "passive"))
      (node (ref "R30") (pin "2") (pinfunction "2_2") (pintype "passive"))
    )
    (net (code "25") (name "Net-(C17-Pad1)") (class "Default")
      (node (ref "C17") (pin "1") (pinfunction "1_1") (pintype "passive"))
      (node (ref "C18") (pin "1") (pinfunction "1_1") (pintype "passive"))
      (node (ref "R34") (pin "2") (pinfunction "2_2") (pintype "passive"))
      (node (ref "R35") (pin "2") (pinfunction "2_2") (pintype "passive"))
    )
    (net (code "26") (name "Net-(C19-Pad1)") (class "Default")
      (node (ref "C19") (pin "1") (pinfunction "1_1") (pintype "passive"))
      (node (ref "C20") (pin "1") (pinfunction "1_1") (pintype "passive"))
      (node (ref "R37") (pin "2") (pinfunction "2_2") (pintype "passive"))
      (node (ref "R38") (pin "2") (pinfunction "2_2") (pintype "passive"))
    )
    (net (code "27") (name "Net-(J1-RING)") (class "Default")
      (node (ref "J1") (pin "3") (pinfunction "RING_3") (pintype "passive"))
      (node (ref "R48") (pin "1") (pinfunction "1_1") (pintype "passive"))
    )
    (net (code "28") (name "Net-(S1-COMMON)") (class "Default")
      (node (ref "P1") (pin "2") (pinfunction "2_2") (pintype "passive"))
      (node (ref "S1") (pin "1") (pinfunction "COMMON_1") (pintype "passive"))
    )
    (net (code "29") (name "Net-(U1-1IN-)") (class "Default")
      (node (ref "C2") (pin "2") (pinfunction "2_2") (pintype "passive"))
      (node (ref "R3") (pin "1") (pinfunction "1_1") (pintype "passive"))
      (node (ref "U1") (pin "2") (pinfunction "1IN-_2") (pintype "input"))
    )
    (net (code "30") (name "Net-(U1-1OUT)") (class "Default")
      (node (ref "C1") (pin "2") (pinfunction "2_2") (pintype "passive"))
      (node (ref "R3") (pin "2") (pinfunction "2_2") (pintype "passive"))
      (node (ref "R4") (pin "1") (pinfunction "1_1") (pintype "passive"))
      (node (ref "U1") (pin "1") (pinfunction "1OUT_1") (pintype "output"))
    )
    (net (code "31") (name "Net-(U1-2IN-)") (class "Default")
      (node (ref "C4") (pin "2") (pinfunction "2_2") (pintype "passive"))
      (node (ref "R6") (pin "1") (pinfunction "1_1") (pintype "passive"))
      (node (ref "U1") (pin "6") (pinfunction "2IN-_6") (pintype "input"))
    )
    (net (code "32") (name "Net-(U1-2OUT)") (class "Default")
      (node (ref "C3") (pin "2") (pinfunction "2_2") (pintype "passive"))
      (node (ref "R6") (pin "2") (pinfunction "2_2") (pintype "passive"))
      (node (ref "R7") (pin "2") (pinfunction "2_2") (pintype "passive"))
      (node (ref "U1") (pin "7") (pinfunction "2OUT_7") (pintype "output"))
    )
    (net (code "33") (name "Net-(U2-1IN-)") (class "Default")
      (node (ref "C6") (pin "2") (pinfunction "2_2") (pintype "passive"))
      (node (ref "R11") (pin "1") (pinfunction "1_1") (pintype "passive"))
      (node (ref "U2") (pin "2") (pinfunction "1IN-_2") (pintype "input"))
    )
    (net (code "34") (name "Net-(U2-1OUT)") (class "Default")
      (node (ref "C5") (pin "2") (pinfunction "2_2") (pintype "passive"))
      (node (ref "R11") (pin "2") (pinfunction "2_2") (pintype "passive"))
      (node (ref "R12") (pin "2") (pinfunction "2_2") (pintype "passive"))
      (node (ref "U2") (pin "1") (pinfunction "1OUT_1") (pintype "output"))
    )
    (net (code "35") (name "Net-(U2-2IN-)") (class "Default")
      (node (ref "C8") (pin "2") (pinfunction "2_2") (pintype "passive"))
      (node (ref "R14") (pin "1") (pinfunction "1_1") (pintype "passive"))
      (node (ref "U2") (pin "6") (pinfunction "2IN-_6") (pintype "input"))
    )
    (net (code "36") (name "Net-(U2-2OUT)") (class "Default")
      (node (ref "C7") (pin "2") (pinfunction "2_2") (pintype "passive"))
      (node (ref "R14") (pin "2") (pinfunction "2_2") (pintype "passive"))
      (node (ref "R15") (pin "1") (pinfunction "1_1") (pintype "passive"))
      (node (ref "U2") (pin "7") (pinfunction "2OUT_7") (pintype "output"))
    )
    (net (code "37") (name "Net-(U4-1IN-)") (class "Default")
      (node (ref "C10") (pin "2") (pinfunction "2_2") (pintype "passive"))
      (node (ref "R19") (pin "1") (pinfunction "1_1") (pintype "passive"))
      (node (ref "U4") (pin "2") (pinfunction "1IN-_2") (pintype "input"))
    )
    (net (code "38") (name "Net-(U4-1OUT)") (class "Default")
      (node (ref "C9") (pin "2") (pinfunction "2_2") (pintype "passive"))
      (node (ref "R19") (pin "2") (pinfunction "2_2") (pintype "passive"))
      (node (ref "R20") (pin "1") (pinfunction "1_1") (pintype "passive"))
      (node (ref "U4") (pin "1") (pinfunction "1OUT_1") (pintype "output"))
    )
    (net (code "39") (name "Net-(U4-2IN-)") (class "Default")
      (node (ref "C12") (pin "2") (pinfunction "2_2") (pintype "passive"))
      (node (ref "R22") (pin "1") (pinfunction "1_1") (pintype "passive"))
      (node (ref "U4") (pin "6") (pinfunction "2IN-_6") (pintype "input"))
    )
    (net (code "40") (name "Net-(U4-2OUT)") (class "Default")
      (node (ref "C11") (pin "2") (pinfunction "2_2") (pintype "passive"))
      (node (ref "R22") (pin "2") (pinfunction "2_2") (pintype "passive"))
      (node (ref "R23") (pin "2") (pinfunction "2_2") (pintype "passive"))
      (node (ref "U4") (pin "7") (pinfunction "2OUT_7") (pintype "output"))
    )
    (net (code "41") (name "Net-(U5-1IN-)") (class "Default")
      (node (ref "C14") (pin "2") (pinfunction "2_2") (pintype "passive"))
      (node (ref "R28") (pin "1") (pinfunction "1_1") (pintype "passive"))
      (node (ref "U5") (pin "2") (pinfunction "1IN-_2") (pintype "input"))
    )
    (net (code "42") (name "Net-(U5-1OUT)") (class "Default")
      (node (ref "C13") (pin "2") (pinfunction "2_2") (pintype "passive"))
      (node (ref "R28") (pin "2") (pinfunction "2_2") (pintype "passive"))
      (node (ref "R29") (pin "1") (pinfunction "1_1") (pintype "passive"))
      (node (ref "U5") (pin "1") (pinfunction "1OUT_1") (pintype "output"))
    )
    (net (code "43") (name "Net-(U5-2IN-)") (class "Default")
      (node (ref "C16") (pin "2") (pinfunction "2_2") (pintype "passive"))
      (node (ref "R31") (pin "1") (pinfunction "1_1") (pintype "passive"))
      (node (ref "U5") (pin "6") (pinfunction "2IN-_6") (pintype "input"))
    )
    (net (code "44") (name "Net-(U5-2OUT)") (class "Default")
      (node (ref "C15") (pin "2") (pinfunction "2_2") (pintype "passive"))
      (node (ref "R31") (pin "2") (pinfunction "2_2") (pintype "passive"))
      (node (ref "R32") (pin "2") (pinfunction "2_2") (pintype "passive"))
      (node (ref "U5") (pin "7") (pinfunction "2OUT_7") (pintype "output"))
    )
    (net (code "45") (name "Net-(U7-1IN-)") (class "Default")
      (node (ref "C18") (pin "2") (pinfunction "2_2") (pintype "passive"))
      (node (ref "R36") (pin "1") (pinfunction "1_1") (pintype "passive"))
      (node (ref "U7") (pin "2") (pinfunction "1IN-_2") (pintype "input"))
    )
    (net (code "46") (name "Net-(U7-1OUT)") (class "Default")
      (node (ref "C17") (pin "2") (pinfunction "2_2") (pintype "passive"))
      (node (ref "R36") (pin "2") (pinfunction "2_2") (pintype "passive"))
      (node (ref "R37") (pin "1") (pinfunction "1_1") (pintype "passive"))
      (node (ref "U7") (pin "1") (pinfunction "1OUT_1") (pintype "output"))
    )
    (net (code "47") (name "Net-(U7-2IN-)") (class "Default")
      (node (ref "C20") (pin "2") (pinfunction "2_2") (pintype "passive"))
      (node (ref "R39") (pin "2") (pinfunction "2_2") (pintype "passive"))
      (node (ref "U7") (pin "6") (pinfunction "2IN-_6") (pintype "input"))
    )
    (net (code "48") (name "Net-(U7-2OUT)") (class "Default")
      (node (ref "C19") (pin "2") (pinfunction "2_2") (pintype "passive"))
      (node (ref "R39") (pin "1") (pinfunction "1_1") (pintype "passive"))
      (node (ref "R40") (pin "2") (pinfunction "2_2") (pintype "passive"))
      (node (ref "U7") (pin "7") (pinfunction "2OUT_7") (pintype "output"))
    )
    (net (code "49") (name "Net-(U9-1IN-)") (class "Default")
      (node (ref "R50") (pin "1") (pinfunction "1_1") (pintype "passive"))
      (node (ref "R51") (pin "1") (pinfunction "1_1") (pintype "passive"))
      (node (ref "U9") (pin "2") (pinfunction "1IN-_2") (pintype "input"))
    )
    (net (code "50") (name "Net-(U9-1IN_+)") (class "Default")
      (node (ref "R48") (pin "2") (pinfunction "2_2") (pintype "passive"))
      (node (ref "R49") (pin "1") (pinfunction "1_1") (pintype "passive"))
      (node (ref "U9") (pin "3") (pinfunction "1IN_+_3") (pintype "input"))
    )
    (net (code "51") (name "Net-(U9-1OUT)") (class "Default")
      (node (ref "R1") (pin "1") (pinfunction "1_1") (pintype "passive"))
      (node (ref "R17") (pin "1") (pinfunction "1_1") (pintype "passive"))
      (node (ref "R26") (pin "1") (pinfunction "1_1") (pintype "passive"))
      (node (ref "R34") (pin "1") (pinfunction "1_1") (pintype "passive"))
      (node (ref "R51") (pin "2") (pinfunction "2_2") (pintype "passive"))
      (node (ref "R9") (pin "2") (pinfunction "2_2") (pintype "passive"))
      (node (ref "U9") (pin "1") (pinfunction "1OUT_1") (pintype "output"))
    )
    (net (code "52") (name "unconnected-(J1-NO_PIN-Pad10)") (class "Default")
      (node (ref "J1") (pin "10") (pinfunction "NO_PIN_10") (pintype "passive"))
    )
    (net (code "53") (name "unconnected-(J1-NO_PIN_-Pad11)") (class "Default")
      (node (ref "J1") (pin "11") (pinfunction "NO_PIN__11") (pintype "passive"))
    )
    (net (code "54") (name "unconnected-(J1-TIP-Pad2)") (class "Default")
      (node (ref "J1") (pin "2") (pinfunction "TIP_2") (pintype "passive"))
    )
    (net (code "55") (name "unconnected-(J2-NO_PIN-Pad10)") (class "Default")
      (node (ref "J2") (pin "10") (pinfunction "NO_PIN_10") (pintype "passive"))
    )
    (net (code "56") (name "unconnected-(J2-NO_PIN_-Pad11)") (class "Default")
      (node (ref "J2") (pin "11") (pinfunction "NO_PIN__11") (pintype "passive"))
    )
    (net (code "57") (name "unconnected-(J2-TIP-Pad2)") (class "Default")
      (node (ref "J2") (pin "2") (pinfunction "TIP_2") (pintype "passive"))
    )
    (net (code "58") (name "unconnected-(U9-2OUT-Pad7)") (class "Default")
      (node (ref "U9") (pin "7") (pinfunction "2OUT_7") (pintype "output"))
    )
  )
)
